# eoncontrol.net
KiCad netlist of a schematic drawn in EAGLE
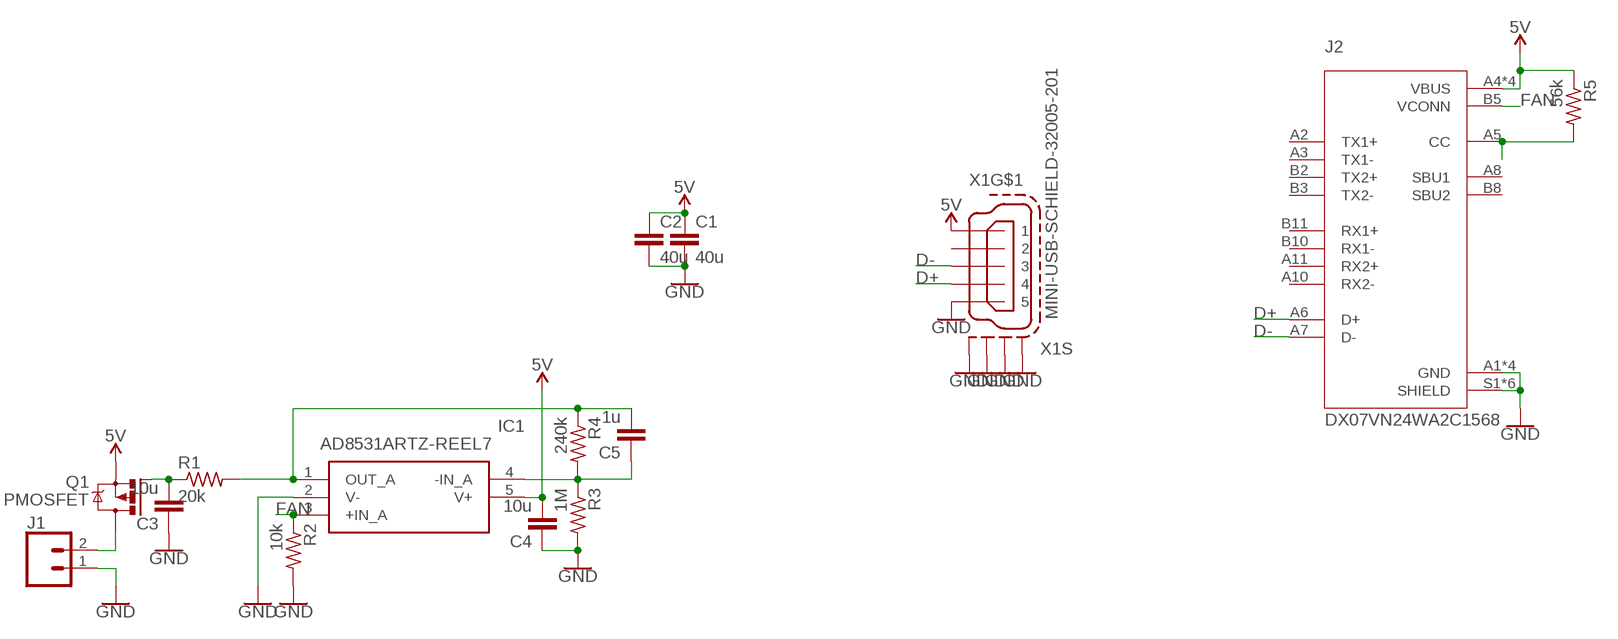
[diagram p0: schematic, sheet 1]

(export (version "E")
  (design (tool "Eeschema 10.0.6"))
  (components
    (comp (ref "C1")
      (value "40u")
      (footprint "eagle-import:C1206")
      (libsource (lib "eagle-import") (part "C-EUC1206"))
    )
    (comp (ref "C2")
      (value "40u")
      (footprint "eagle-import:C1206")
      (libsource (lib "eagle-import") (part "C-EUC1206"))
    )
    (comp (ref "C3")
      (value "10u")
      (footprint "eagle-import:0603-C")
      (libsource (lib "eagle-import") (part "C0603"))
    )
    (comp (ref "C4")
      (value "10u")
      (footprint "eagle-import:0603-C")
      (libsource (lib "eagle-import") (part "C0603"))
    )
    (comp (ref "C5")
      (value "1u")
      (footprint "eagle-import:0603-C")
      (libsource (lib "eagle-import") (part "C0603"))
    )
    (comp (ref "IC1")
      (value "AD8531ARTZ-REEL7")
      (footprint "eagle-import:SOT95P280X145-5N")
      (fields (field (name "MOUSER_PART_NUMBER") "584-AD8531ARTZ-R7"))
      (libsource (lib "eagle-import") (part "AD8531ARTZ-REEL7"))
    )
    (comp (ref "J1")
      (value "CONN_02")
      (footprint "eagle-import:1X02")
      (libsource (lib "eagle-import") (part "CONN_02"))
    )
    (comp (ref "J2")
      (value "DX07VN24WA2C1568")
      (footprint "eagle-import:JAE_DX07VN24WA2C1568")
      (fields (field (name "MF") "JAE Electronics"))
      (libsource (lib "eagle-import") (part "DX07VN24WA2C1568"))
    )
    (comp (ref "Q1")
      (value "PMOSFET")
      (footprint "eagle-import:SOT23")
      (libsource (lib "eagle-import") (part "PMOSFETSOT23_"))
    )
    (comp (ref "R1")
      (value "20k")
      (footprint "eagle-import:0603-R")
      (libsource (lib "eagle-import") (part "R0603"))
    )
    (comp (ref "R2")
      (value "10k")
      (footprint "eagle-import:0603-R")
      (libsource (lib "eagle-import") (part "R0603"))
    )
    (comp (ref "R3")
      (value "1M")
      (footprint "eagle-import:0603-R")
      (libsource (lib "eagle-import") (part "R0603"))
    )
    (comp (ref "R4")
      (value "240k")
      (footprint "eagle-import:0603-R")
      (libsource (lib "eagle-import") (part "R0603"))
    )
    (comp (ref "R5")
      (value "56k")
      (footprint "eagle-import:0603-R")
      (libsource (lib "eagle-import") (part "R0603"))
    )
    (comp (ref "X1")
      (value "MINI-USB-SCHIELD-32005-201")
      (footprint "eagle-import:32005-201")
      (libsource (lib "eagle-import") (part "MINI-USB-SCHIELD-32005-201"))
    )
  )
  (nets
    (net (code "1") (name "/D+") (class "Default")
      (node (ref "J2") (pin "A6") (pinfunction "D+_A6") (pintype "bidirectional"))
      (node (ref "X1") (pin "4") (pinfunction "4_4") (pintype "passive"))
    )
    (net (code "2") (name "/D-") (class "Default")
      (node (ref "J2") (pin "A7") (pinfunction "D-_A7") (pintype "bidirectional"))
      (node (ref "X1") (pin "3") (pinfunction "3_3") (pintype "passive"))
    )
    (net (code "3") (name "/FAN") (class "Default")
      (node (ref "IC1") (pin "3") (pinfunction "+IN_A_3") (pintype "bidirectional"))
      (node (ref "J2") (pin "B5") (pinfunction "VCONN_B5") (pintype "power_in"))
      (node (ref "R2") (pin "1") (pinfunction "1_1") (pintype "passive"))
    )
    (net (code "4") (name "5V") (class "Default")
      (node (ref "C1") (pin "1") (pinfunction "1_1") (pintype "passive"))
      (node (ref "C2") (pin "1") (pinfunction "1_1") (pintype "passive"))
      (node (ref "C4") (pin "2") (pinfunction "2_2") (pintype "passive"))
      (node (ref "IC1") (pin "5") (pinfunction "V+_5") (pintype "bidirectional"))
      (node (ref "J2") (pin "A4") (pinfunction "VBUS_A4") (pintype "power_in"))
      (node (ref "J2") (pin "A9") (pinfunction "VBUS_A9") (pintype "power_in"))
      (node (ref "J2") (pin "B4") (pinfunction "VBUS_B4") (pintype "power_in"))
      (node (ref "J2") (pin "B9") (pinfunction "VBUS_B9") (pintype "power_in"))
      (node (ref "Q1") (pin "2") (pinfunction "S_2") (pintype "passive"))
      (node (ref "R5") (pin "1") (pinfunction "1_1") (pintype "passive"))
      (node (ref "X1") (pin "1") (pinfunction "1_1") (pintype "passive"))
    )
    (net (code "5") (name "GND") (class "Default")
      (node (ref "C1") (pin "2") (pinfunction "2_2") (pintype "passive"))
      (node (ref "C2") (pin "2") (pinfunction "2_2") (pintype "passive"))
      (node (ref "C3") (pin "1") (pinfunction "1_1") (pintype "passive"))
      (node (ref "C4") (pin "1") (pinfunction "1_1") (pintype "passive"))
      (node (ref "IC1") (pin "2") (pinfunction "V-_2") (pintype "bidirectional"))
      (node (ref "J1") (pin "1") (pinfunction "1_1") (pintype "passive"))
      (node (ref "J2") (pin "A1") (pinfunction "GND_A1") (pintype "power_in"))
      (node (ref "J2") (pin "A12") (pinfunction "GND_A12") (pintype "power_in"))
      (node (ref "J2") (pin "B1") (pinfunction "GND_B1") (pintype "power_in"))
      (node (ref "J2") (pin "B12") (pinfunction "GND_B12") (pintype "power_in"))
      (node (ref "J2") (pin "S1") (pinfunction "SHIELD_S1") (pintype "power_in"))
      (node (ref "J2") (pin "S2") (pinfunction "SHIELD_S2") (pintype "power_in"))
      (node (ref "J2") (pin "S3") (pinfunction "SHIELD_S3") (pintype "power_in"))
      (node (ref "J2") (pin "S4") (pinfunction "SHIELD_S4") (pintype "power_in"))
      (node (ref "J2") (pin "S5") (pinfunction "SHIELD_S5") (pintype "power_in"))
      (node (ref "J2") (pin "S6") (pinfunction "SHIELD_S6") (pintype "power_in"))
      (node (ref "R2") (pin "2") (pinfunction "2_2") (pintype "passive"))
      (node (ref "R3") (pin "2") (pinfunction "2_2") (pintype "passive"))
      (node (ref "X1") (pin "5") (pinfunction "5_5") (pintype "passive"))
      (node (ref "X1") (pin "M1") (pinfunction "S1_M1") (pintype "passive"))
      (node (ref "X1") (pin "M2") (pinfunction "S2_M2") (pintype "passive"))
      (node (ref "X1") (pin "M3") (pinfunction "S3_M3") (pintype "passive"))
      (node (ref "X1") (pin "M4") (pinfunction "S4_M4") (pintype "passive"))
    )
    (net (code "6") (name "Net-(IC1--IN_A)") (class "Default")
      (node (ref "C5") (pin "1") (pinfunction "1_1") (pintype "passive"))
      (node (ref "IC1") (pin "4") (pinfunction "-IN_A_4") (pintype "bidirectional"))
      (node (ref "R3") (pin "1") (pinfunction "1_1") (pintype "passive"))
      (node (ref "R4") (pin "2") (pinfunction "2_2") (pintype "passive"))
    )
    (net (code "7") (name "Net-(IC1-OUT_A)") (class "Default")
      (node (ref "C5") (pin "2") (pinfunction "2_2") (pintype "passive"))
      (node (ref "IC1") (pin "1") (pinfunction "OUT_A_1") (pintype "bidirectional"))
      (node (ref "R1") (pin "2") (pinfunction "2_2") (pintype "passive"))
      (node (ref "R4") (pin "1") (pinfunction "1_1") (pintype "passive"))
    )
    (net (code "8") (name "Net-(J2-CC)") (class "Default")
      (node (ref "J2") (pin "A5") (pinfunction "CC_A5") (pintype "bidirectional"))
      (node (ref "R5") (pin "2") (pinfunction "2_2") (pintype "passive"))
    )
    (net (code "9") (name "Net-(Q1-D)") (class "Default")
      (node (ref "J1") (pin "2") (pinfunction "2_2") (pintype "passive"))
      (node (ref "Q1") (pin "3") (pinfunction "D_3") (pintype "passive"))
    )
    (net (code "10") (name "Net-(Q1-G)") (class "Default")
      (node (ref "C3") (pin "2") (pinfunction "2_2") (pintype "passive"))
      (node (ref "Q1") (pin "1") (pinfunction "G_1") (pintype "passive"))
      (node (ref "R1") (pin "1") (pinfunction "1_1") (pintype "passive"))
    )
    (net (code "11") (name "unconnected-(J2-RX1+-PadB11)") (class "Default")
      (node (ref "J2") (pin "B11") (pinfunction "RX1+_B11") (pintype "bidirectional"))
    )
    (net (code "12") (name "unconnected-(J2-RX1--PadB10)") (class "Default")
      (node (ref "J2") (pin "B10") (pinfunction "RX1-_B10") (pintype "bidirectional"))
    )
    (net (code "13") (name "unconnected-(J2-RX2+-PadA11)") (class "Default")
      (node (ref "J2") (pin "A11") (pinfunction "RX2+_A11") (pintype "bidirectional"))
    )
    (net (code "14") (name "unconnected-(J2-RX2--PadA10)") (class "Default")
      (node (ref "J2") (pin "A10") (pinfunction "RX2-_A10") (pintype "bidirectional"))
    )
    (net (code "15") (name "unconnected-(J2-SBU1-PadA8)") (class "Default")
      (node (ref "J2") (pin "A8") (pinfunction "SBU1_A8") (pintype "bidirectional"))
    )
    (net (code "16") (name "unconnected-(J2-SBU2-PadB8)") (class "Default")
      (node (ref "J2") (pin "B8") (pinfunction "SBU2_B8") (pintype "bidirectional"))
    )
    (net (code "17") (name "unconnected-(J2-TX1+-PadA2)") (class "Default")
      (node (ref "J2") (pin "A2") (pinfunction "TX1+_A2") (pintype "bidirectional"))
    )
    (net (code "18") (name "unconnected-(J2-TX1--PadA3)") (class "Default")
      (node (ref "J2") (pin "A3") (pinfunction "TX1-_A3") (pintype "bidirectional"))
    )
    (net (code "19") (name "unconnected-(J2-TX2+-PadB2)") (class "Default")
      (node (ref "J2") (pin "B2") (pinfunction "TX2+_B2") (pintype "bidirectional"))
    )
    (net (code "20") (name "unconnected-(J2-TX2--PadB3)") (class "Default")
      (node (ref "J2") (pin "B3") (pinfunction "TX2-_B3") (pintype "bidirectional"))
    )
    (net (code "21") (name "unconnected-(X1-Pad2)") (class "Default")
      (node (ref "X1") (pin "2") (pinfunction "2_2") (pintype "passive"))
    )
  )
)
